# Sheet3.net
KiCad netlist of a schematic drawn in Altium Designer
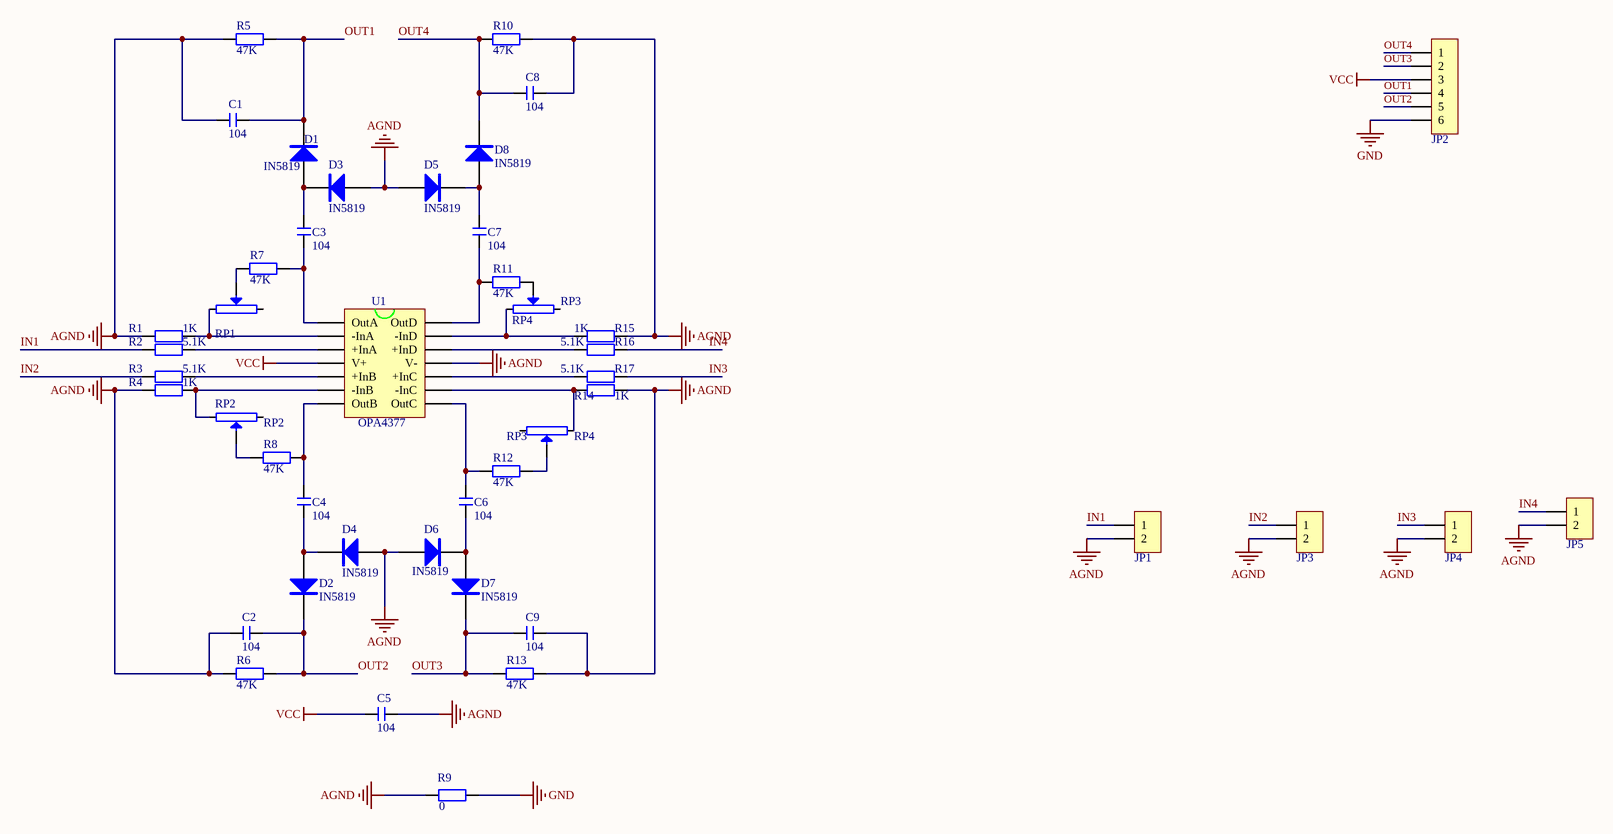
[diagram p0: Sheet3.SchDoc]

(export (version "E")
  (design (tool "Eeschema 10.0.6"))
  (components
    (comp (ref "C1")
      (value "104")
      (footprint "R 0805_M")
      (description "贴片电容")
      (libsource (lib "0.1 - 电阻-电容-电感") (part "C"))
    )
    (comp (ref "C2")
      (value "104")
      (footprint "R 0805_M")
      (description "贴片电容")
      (libsource (lib "0.1 - 电阻-电容-电感") (part "C"))
    )
    (comp (ref "C3")
      (value "104")
      (footprint "R 0805_M")
      (description "贴片电容")
      (libsource (lib "0.1 - 电阻-电容-电感") (part "C"))
    )
    (comp (ref "C4")
      (value "104")
      (footprint "R 0805_M")
      (description "贴片电容")
      (libsource (lib "0.1 - 电阻-电容-电感") (part "C"))
    )
    (comp (ref "C5")
      (value "104")
      (footprint "R 0805_M")
      (description "贴片电容")
      (libsource (lib "0.1 - 电阻-电容-电感") (part "C"))
    )
    (comp (ref "C6")
      (value "104")
      (footprint "R 0805_M")
      (description "贴片电容")
      (libsource (lib "0.1 - 电阻-电容-电感") (part "C"))
    )
    (comp (ref "C7")
      (value "104")
      (footprint "R 0805_M")
      (description "贴片电容")
      (libsource (lib "0.1 - 电阻-电容-电感") (part "C"))
    )
    (comp (ref "C8")
      (value "104")
      (footprint "R 0805_M")
      (description "贴片电容")
      (libsource (lib "0.1 - 电阻-电容-电感") (part "C"))
    )
    (comp (ref "C9")
      (value "104")
      (footprint "R 0805_M")
      (description "贴片电容")
      (libsource (lib "0.1 - 电阻-电容-电感") (part "C"))
    )
    (comp (ref "D1") (value "IN5819") (footprint "SOD-123") (libsource (lib "YUNFANG") (part "IN5819")))
    (comp (ref "D2") (value "IN5819") (footprint "SOD-123") (libsource (lib "YUNFANG") (part "IN5819")))
    (comp (ref "D3") (value "IN5819") (footprint "SOD-123") (libsource (lib "YUNFANG") (part "IN5819")))
    (comp (ref "D4") (value "IN5819") (footprint "SOD-123") (libsource (lib "YUNFANG") (part "IN5819")))
    (comp (ref "D5") (value "IN5819") (footprint "SOD-123") (libsource (lib "YUNFANG") (part "IN5819")))
    (comp (ref "D6") (value "IN5819") (footprint "SOD-123") (libsource (lib "YUNFANG") (part "IN5819")))
    (comp (ref "D7") (value "IN5819") (footprint "SOD-123") (libsource (lib "YUNFANG") (part "IN5819")))
    (comp (ref "D8") (value "IN5819") (footprint "SOD-123") (libsource (lib "YUNFANG") (part "IN5819")))
    (comp (ref "JP1")
      (value "HDR-1X2")
      (footprint "XH2.54-LI-2P")
      (description "2P接插件")
      (fields (field (name "版权归属") "封装库来自淘宝 ID：黄晶宝石"))
      (libsource (lib "5.4 - 接插件-脚距2.54 (100mil) ") (part "Header 2"))
    )
    (comp (ref "JP2")
      (value "HDR-1X6")
      (footprint "HDR2.54-LI-6P")
      (description "6P接插件")
      (fields (field (name "版权归属") "源创客"))
      (libsource (lib "4.5   - 接插件-脚距2.54") (part "Header 6"))
    )
    (comp (ref "JP3")
      (value "HDR-1X2")
      (footprint "XH2.54-LI-2P")
      (description "2P接插件")
      (fields (field (name "版权归属") "封装库来自淘宝 ID：黄晶宝石"))
      (libsource (lib "5.4 - 接插件-脚距2.54 (100mil) ") (part "Header 2"))
    )
    (comp (ref "JP4")
      (value "HDR-1X2")
      (footprint "XH2.54-LI-2P")
      (description "2P接插件")
      (fields (field (name "版权归属") "封装库来自淘宝 ID：黄晶宝石"))
      (libsource (lib "5.4 - 接插件-脚距2.54 (100mil) ") (part "Header 2"))
    )
    (comp (ref "JP5")
      (value "HDR-1X2")
      (footprint "XH2.54-LI-2P")
      (description "2P接插件")
      (fields (field (name "版权归属") "封装库来自淘宝 ID：黄晶宝石"))
      (libsource (lib "5.4 - 接插件-脚距2.54 (100mil) ") (part "Header 2"))
    )
    (comp (ref "R1")
      (value "1K")
      (footprint "R 0805_M")
      (description "Resistor")
      (fields (field (name "PUBLISHER") "Altium Limited"))
      (libsource (lib "YUNFANG") (part "R1"))
    )
    (comp (ref "R2")
      (value "5.1K")
      (footprint "R 0805_M")
      (description "Resistor")
      (fields (field (name "PUBLISHER") "Altium Limited"))
      (libsource (lib "YUNFANG") (part "R13"))
    )
    (comp (ref "R3")
      (value "5.1K")
      (footprint "R 0805_M")
      (description "Resistor")
      (fields (field (name "PUBLISHER") "Altium Limited"))
      (libsource (lib "YUNFANG") (part "R14"))
    )
    (comp (ref "R4")
      (value "1K")
      (footprint "R 0805_M")
      (description "Resistor")
      (fields (field (name "PUBLISHER") "Altium Limited"))
      (libsource (lib "YUNFANG") (part "R2"))
    )
    (comp (ref "R5")
      (value "47K")
      (footprint "R 0805_M")
      (description "Resistor")
      (fields (field (name "PUBLISHER") "Altium Limited"))
      (libsource (lib "YUNFANG") (part "R9"))
    )
    (comp (ref "R6")
      (value "47K")
      (footprint "R 0805_M")
      (description "Resistor")
      (fields (field (name "PUBLISHER") "Altium Limited"))
      (libsource (lib "YUNFANG") (part "R10"))
    )
    (comp (ref "R7")
      (value "47K")
      (footprint "R 0805_M")
      (description "Resistor")
      (fields (field (name "PUBLISHER") "Altium Limited"))
      (libsource (lib "YUNFANG") (part "R5"))
    )
    (comp (ref "R8")
      (value "47K")
      (footprint "R 0805_M")
      (description "Resistor")
      (fields (field (name "PUBLISHER") "Altium Limited"))
      (libsource (lib "YUNFANG") (part "R6"))
    )
    (comp (ref "R9") (value "0") (footprint "14-1210") (libsource (lib "MD_分立元件自定义标准库") (part "RES_MD")))
    (comp (ref "R10")
      (value "47K")
      (footprint "R 0805_M")
      (description "Resistor")
      (fields (field (name "PUBLISHER") "Altium Limited"))
      (libsource (lib "YUNFANG") (part "R12"))
    )
    (comp (ref "R11")
      (value "47K")
      (footprint "R 0805_M")
      (description "Resistor")
      (fields (field (name "PUBLISHER") "Altium Limited"))
      (libsource (lib "YUNFANG") (part "R8"))
    )
    (comp (ref "R12")
      (value "47K")
      (footprint "R 0805_M")
      (description "Resistor")
      (fields (field (name "PUBLISHER") "Altium Limited"))
      (libsource (lib "YUNFANG") (part "R7"))
    )
    (comp (ref "R13")
      (value "47K")
      (footprint "R 0805_M")
      (description "Resistor")
      (fields (field (name "PUBLISHER") "Altium Limited"))
      (libsource (lib "YUNFANG") (part "R11"))
    )
    (comp (ref "R14")
      (value "1K")
      (footprint "R 0805_M")
      (description "Resistor")
      (fields (field (name "PUBLISHER") "Altium Limited"))
      (libsource (lib "YUNFANG") (part "R3"))
    )
    (comp (ref "R15")
      (value "1K")
      (footprint "R 0805_M")
      (description "Resistor")
      (fields (field (name "PUBLISHER") "Altium Limited"))
      (libsource (lib "YUNFANG") (part "R4"))
    )
    (comp (ref "R16")
      (value "5.1K")
      (footprint "R 0805_M")
      (description "Resistor")
      (fields (field (name "PUBLISHER") "Altium Limited"))
      (libsource (lib "YUNFANG") (part "R16"))
    )
    (comp (ref "R17")
      (value "5.1K")
      (footprint "R 0805_M")
      (description "Resistor")
      (fields (field (name "PUBLISHER") "Altium Limited"))
      (libsource (lib "YUNFANG") (part "R15"))
    )
    (comp (ref "RP1") (value "RP1") (footprint "3269W_滑动变阻器") (libsource (lib "YUNFANG") (part "RP1")))
    (comp (ref "RP2") (value "RP2") (footprint "3269W_滑动变阻器") (libsource (lib "YUNFANG") (part "RP2")))
    (comp (ref "RP3") (value "RP4") (footprint "3269W_滑动变阻器") (libsource (lib "YUNFANG") (part "RP3")))
    (comp (ref "RP4") (value "RP3") (footprint "3269W_滑动变阻器") (libsource (lib "YUNFANG") (part "RP4")))
    (comp (ref "U1")
      (value "OPA4377")
      (footprint "PCBComponent_1")
      (libsource (lib "YUNFANG") (part "OPA4377"))
    )
  )
  (nets
    (net (code "1") (name "/IN1") (class "Default")
      (node (ref "JP1") (pin "1") (pinfunction "1_1") (pintype "passive"))
      (node (ref "R2") (pin "1") (pinfunction "1_1") (pintype "passive"))
    )
    (net (code "2") (name "/IN2") (class "Default")
      (node (ref "JP3") (pin "1") (pinfunction "1_1") (pintype "passive"))
      (node (ref "R3") (pin "1") (pinfunction "1_1") (pintype "passive"))
    )
    (net (code "3") (name "/IN3") (class "Default")
      (node (ref "JP4") (pin "1") (pinfunction "1_1") (pintype "passive"))
      (node (ref "R17") (pin "2") (pinfunction "2_2") (pintype "passive"))
    )
    (net (code "4") (name "/IN4") (class "Default")
      (node (ref "JP5") (pin "1") (pinfunction "1_1") (pintype "passive"))
      (node (ref "R16") (pin "2") (pinfunction "2_2") (pintype "passive"))
    )
    (net (code "5") (name "/OUT1") (class "Default")
      (node (ref "C1") (pin "2") (pinfunction "2_2") (pintype "passive"))
      (node (ref "D1") (pin "2") (pinfunction "2_2") (pintype "passive"))
      (node (ref "JP2") (pin "4") (pinfunction "4_4") (pintype "passive"))
      (node (ref "R5") (pin "2") (pinfunction "2_2") (pintype "passive"))
    )
    (net (code "6") (name "/OUT2") (class "Default")
      (node (ref "C2") (pin "2") (pinfunction "2_2") (pintype "passive"))
      (node (ref "D2") (pin "2") (pinfunction "2_2") (pintype "passive"))
      (node (ref "JP2") (pin "5") (pinfunction "5_5") (pintype "passive"))
      (node (ref "R6") (pin "2") (pinfunction "2_2") (pintype "passive"))
    )
    (net (code "7") (name "/OUT3") (class "Default")
      (node (ref "C9") (pin "1") (pinfunction "1_1") (pintype "passive"))
      (node (ref "D7") (pin "2") (pinfunction "2_2") (pintype "passive"))
      (node (ref "JP2") (pin "2") (pinfunction "2_2") (pintype "passive"))
      (node (ref "R13") (pin "1") (pinfunction "1_1") (pintype "passive"))
    )
    (net (code "8") (name "/OUT4") (class "Default")
      (node (ref "C8") (pin "1") (pinfunction "1_1") (pintype "passive"))
      (node (ref "D8") (pin "2") (pinfunction "2_2") (pintype "passive"))
      (node (ref "JP2") (pin "1") (pinfunction "1_1") (pintype "passive"))
      (node (ref "R10") (pin "1") (pinfunction "1_1") (pintype "passive"))
    )
    (net (code "9") (name "AGND") (class "Default")
      (node (ref "C1") (pin "1") (pinfunction "1_1") (pintype "passive"))
      (node (ref "C2") (pin "1") (pinfunction "1_1") (pintype "passive"))
      (node (ref "C5") (pin "2") (pinfunction "2_2") (pintype "passive"))
      (node (ref "C8") (pin "2") (pinfunction "2_2") (pintype "passive"))
      (node (ref "C9") (pin "2") (pinfunction "2_2") (pintype "passive"))
      (node (ref "D3") (pin "1") (pinfunction "1_1") (pintype "passive"))
      (node (ref "D4") (pin "1") (pinfunction "1_1") (pintype "passive"))
      (node (ref "D5") (pin "1") (pinfunction "1_1") (pintype "passive"))
      (node (ref "D6") (pin "1") (pinfunction "1_1") (pintype "passive"))
      (node (ref "JP1") (pin "2") (pinfunction "2_2") (pintype "passive"))
      (node (ref "JP3") (pin "2") (pinfunction "2_2") (pintype "passive"))
      (node (ref "JP4") (pin "2") (pinfunction "2_2") (pintype "passive"))
      (node (ref "JP5") (pin "2") (pinfunction "2_2") (pintype "passive"))
      (node (ref "R1") (pin "1") (pinfunction "1_1") (pintype "passive"))
      (node (ref "R10") (pin "2") (pinfunction "2_2") (pintype "passive"))
      (node (ref "R13") (pin "2") (pinfunction "2_2") (pintype "passive"))
      (node (ref "R14") (pin "2") (pinfunction "2_2") (pintype "passive"))
      (node (ref "R15") (pin "2") (pinfunction "2_2") (pintype "passive"))
      (node (ref "R4") (pin "1") (pinfunction "1_1") (pintype "passive"))
      (node (ref "R5") (pin "1") (pinfunction "1_1") (pintype "passive"))
      (node (ref "R6") (pin "1") (pinfunction "1_1") (pintype "passive"))
      (node (ref "R9") (pin "2") (pinfunction "2_2") (pintype "passive"))
      (node (ref "U1") (pin "11") (pinfunction "V-_11") (pintype "passive"))
    )
    (net (code "10") (name "GND") (class "Default")
      (node (ref "JP2") (pin "6") (pinfunction "6_6") (pintype "passive"))
      (node (ref "R9") (pin "1") (pinfunction "vcc_1") (pintype "passive"))
    )
    (net (code "11") (name "Net-(C3-Pad2)") (class "Default")
      (node (ref "C3") (pin "2") (pinfunction "2_2") (pintype "passive"))
      (node (ref "D1") (pin "1") (pinfunction "1_1") (pintype "passive"))
      (node (ref "D3") (pin "2") (pinfunction "2_2") (pintype "passive"))
    )
    (net (code "12") (name "Net-(C4-Pad1)") (class "Default")
      (node (ref "C4") (pin "1") (pinfunction "1_1") (pintype "passive"))
      (node (ref "D2") (pin "1") (pinfunction "1_1") (pintype "passive"))
      (node (ref "D4") (pin "2") (pinfunction "2_2") (pintype "passive"))
    )
    (net (code "13") (name "Net-(C6-Pad1)") (class "Default")
      (node (ref "C6") (pin "1") (pinfunction "1_1") (pintype "passive"))
      (node (ref "D6") (pin "2") (pinfunction "2_2") (pintype "passive"))
      (node (ref "D7") (pin "1") (pinfunction "1_1") (pintype "passive"))
    )
    (net (code "14") (name "Net-(C7-Pad2)") (class "Default")
      (node (ref "C7") (pin "2") (pinfunction "2_2") (pintype "passive"))
      (node (ref "D5") (pin "2") (pinfunction "2_2") (pintype "passive"))
      (node (ref "D8") (pin "1") (pinfunction "1_1") (pintype "passive"))
    )
    (net (code "15") (name "Net-(R7-Pad1)") (class "Default")
      (node (ref "R7") (pin "1") (pinfunction "1_1") (pintype "passive"))
      (node (ref "RP1") (pin "3") (pintype "passive"))
    )
    (net (code "16") (name "Net-(R8-Pad1)") (class "Default")
      (node (ref "R8") (pin "1") (pinfunction "1_1") (pintype "passive"))
      (node (ref "RP2") (pin "3") (pintype "passive"))
    )
    (net (code "17") (name "Net-(R11-Pad2)") (class "Default")
      (node (ref "R11") (pin "2") (pinfunction "2_2") (pintype "passive"))
      (node (ref "RP4") (pin "3") (pintype "passive"))
    )
    (net (code "18") (name "Net-(R12-Pad2)") (class "Default")
      (node (ref "R12") (pin "2") (pinfunction "2_2") (pintype "passive"))
      (node (ref "RP3") (pin "3") (pintype "passive"))
    )
    (net (code "19") (name "Net-(U1-+InA)") (class "Default")
      (node (ref "R2") (pin "2") (pinfunction "2_2") (pintype "passive"))
      (node (ref "U1") (pin "3") (pinfunction "+InA_3") (pintype "passive"))
    )
    (net (code "20") (name "Net-(U1-+InB)") (class "Default")
      (node (ref "R3") (pin "2") (pinfunction "2_2") (pintype "passive"))
      (node (ref "U1") (pin "5") (pinfunction "+InB_5") (pintype "passive"))
    )
    (net (code "21") (name "Net-(U1-+InC)") (class "Default")
      (node (ref "R17") (pin "1") (pinfunction "1_1") (pintype "passive"))
      (node (ref "U1") (pin "10") (pinfunction "+InC_10") (pintype "passive"))
    )
    (net (code "22") (name "Net-(U1-+InD)") (class "Default")
      (node (ref "R16") (pin "1") (pinfunction "1_1") (pintype "passive"))
      (node (ref "U1") (pin "12") (pinfunction "+InD_12") (pintype "passive"))
    )
    (net (code "23") (name "Net-(U1--InA)") (class "Default")
      (node (ref "R1") (pin "2") (pinfunction "2_2") (pintype "passive"))
      (node (ref "RP1") (pin "1") (pintype "passive"))
      (node (ref "U1") (pin "2") (pinfunction "-InA_2") (pintype "passive"))
    )
    (net (code "24") (name "Net-(U1--InB)") (class "Default")
      (node (ref "R4") (pin "2") (pinfunction "2_2") (pintype "passive"))
      (node (ref "RP2") (pin "2") (pintype "passive"))
      (node (ref "U1") (pin "6") (pinfunction "-InB_6") (pintype "passive"))
    )
    (net (code "25") (name "Net-(U1--InC)") (class "Default")
      (node (ref "R14") (pin "1") (pinfunction "1_1") (pintype "passive"))
      (node (ref "RP3") (pin "1") (pintype "passive"))
      (node (ref "U1") (pin "9") (pinfunction "-InC_9") (pintype "passive"))
    )
    (net (code "26") (name "Net-(U1--InD)") (class "Default")
      (node (ref "R15") (pin "1") (pinfunction "1_1") (pintype "passive"))
      (node (ref "RP4") (pin "1") (pintype "passive"))
      (node (ref "U1") (pin "13") (pinfunction "-InD_13") (pintype "passive"))
    )
    (net (code "27") (name "Net-(U1-OutA)") (class "Default")
      (node (ref "C3") (pin "1") (pinfunction "1_1") (pintype "passive"))
      (node (ref "R7") (pin "2") (pinfunction "2_2") (pintype "passive"))
      (node (ref "U1") (pin "1") (pinfunction "OutA_1") (pintype "passive"))
    )
    (net (code "28") (name "Net-(U1-OutB)") (class "Default")
      (node (ref "C4") (pin "2") (pinfunction "2_2") (pintype "passive"))
      (node (ref "R8") (pin "2") (pinfunction "2_2") (pintype "passive"))
      (node (ref "U1") (pin "7") (pinfunction "OutB_7") (pintype "passive"))
    )
    (net (code "29") (name "Net-(U1-OutC)") (class "Default")
      (node (ref "C6") (pin "2") (pinfunction "2_2") (pintype "passive"))
      (node (ref "R12") (pin "1") (pinfunction "1_1") (pintype "passive"))
      (node (ref "U1") (pin "8") (pinfunction "OutC_8") (pintype "passive"))
    )
    (net (code "30") (name "Net-(U1-OutD)") (class "Default")
      (node (ref "C7") (pin "1") (pinfunction "1_1") (pintype "passive"))
      (node (ref "R11") (pin "1") (pinfunction "1_1") (pintype "passive"))
      (node (ref "U1") (pin "14") (pinfunction "OutD_14") (pintype "passive"))
    )
    (net (code "31") (name "VCC") (class "Default")
      (node (ref "C5") (pin "1") (pinfunction "1_1") (pintype "passive"))
      (node (ref "JP2") (pin "3") (pinfunction "3_3") (pintype "passive"))
      (node (ref "U1") (pin "4") (pinfunction "V+_4") (pintype "passive"))
    )
    (net (code "32") (name "unconnected-(RP1-Pad2)") (class "Default")
      (node (ref "RP1") (pin "2") (pintype "passive"))
    )
    (net (code "33") (name "unconnected-(RP2-Pad1)") (class "Default")
      (node (ref "RP2") (pin "1") (pintype "passive"))
    )
    (net (code "34") (name "unconnected-(RP3-Pad2)") (class "Default")
      (node (ref "RP3") (pin "2") (pintype "passive"))
    )
    (net (code "35") (name "unconnected-(RP4-Pad2)") (class "Default")
      (node (ref "RP4") (pin "2") (pintype "passive"))
    )
  )
)
